# bldc_driver.net
KiCad netlist of a schematic drawn in Altium Designer
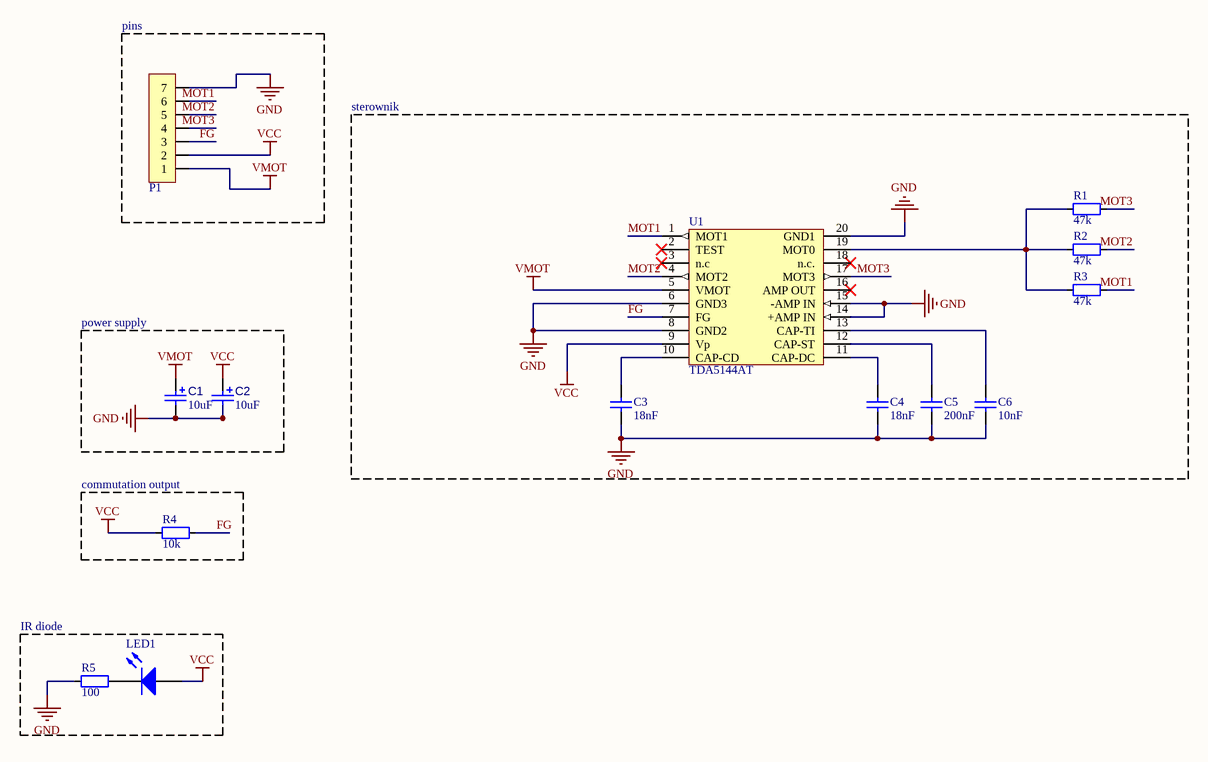
[diagram p0: bldc_driver.SchDoc]

(export (version "E")
  (design (tool "Eeschema 10.0.6"))
  (components
    (comp (ref "C1")
      (value "10uF")
      (footprint "Con_SMD_5x5.5")
      (description "Polar capacitor")
      (libsource (lib "altium_library_onyks") (part "Cap_Pol"))
    )
    (comp (ref "C2")
      (value "10uF")
      (footprint "Con_SMD_5x5.5")
      (description "Polar capacitor")
      (libsource (lib "altium_library_onyks") (part "Cap_Pol"))
    )
    (comp (ref "C3")
      (value "18nF")
      (footprint "0603_CAP")
      (description "Ceramic capacitor")
      (fields (field (name "Comment") "Cap"))
      (libsource (lib "altium_library_onyks") (part "Cap"))
    )
    (comp (ref "C4")
      (value "18nF")
      (footprint "0603_CAP")
      (description "Ceramic capacitor")
      (fields (field (name "Comment") "Cap"))
      (libsource (lib "altium_library_onyks") (part "Cap"))
    )
    (comp (ref "C5")
      (value "200nF")
      (footprint "0603_CAP")
      (description "Ceramic capacitor")
      (fields (field (name "Comment") "Cap"))
      (libsource (lib "altium_library_onyks") (part "Cap"))
    )
    (comp (ref "C6")
      (value "10nF")
      (footprint "0603_CAP")
      (description "Ceramic capacitor")
      (fields (field (name "Comment") "Cap"))
      (libsource (lib "altium_library_onyks") (part "Cap"))
    )
    (comp (ref "LED1")
      (value "RED")
      (footprint "VSMB2020X01")
      (description "Light-emitting diode")
      (libsource (lib "altium_library_onyks") (part "LED"))
    )
    (comp (ref "P1")
      (value "HDR1X7")
      (footprint "HDR1X7")
      (description "Header, 7-Pin")
      (fields (field (name "PUBLISHER") "Altium Limited"))
      (libsource (lib "altium_library_onyks") (part "HDR1X7"))
    )
    (comp (ref "R1")
      (value "47k")
      (footprint "0603_RES")
      (description "Resistior")
      (libsource (lib "altium_library_onyks") (part "RES"))
    )
    (comp (ref "R2")
      (value "47k")
      (footprint "0603_RES")
      (description "Resistior")
      (libsource (lib "altium_library_onyks") (part "RES"))
    )
    (comp (ref "R3")
      (value "47k")
      (footprint "0603_RES")
      (description "Resistior")
      (libsource (lib "altium_library_onyks") (part "RES"))
    )
    (comp (ref "R4")
      (value "10k")
      (footprint "0603_RES")
      (description "Resistior")
      (libsource (lib "altium_library_onyks") (part "RES"))
    )
    (comp (ref "R5")
      (value "100")
      (footprint "0603_RES")
      (description "Resistior")
      (libsource (lib "altium_library_onyks") (part "RES"))
    )
    (comp (ref "U1")
      (value "TDA5144AT")
      (footprint "SO20")
      (description "driver TDA5144AT")
      (libsource (lib "altium_library_onyks") (part "driver_TDA5144AT"))
    )
  )
  (nets
    (net (code "1") (name "/FG") (class "Default")
      (node (ref "P1") (pin "3") (pinfunction "3_3") (pintype "passive"))
      (node (ref "R4") (pin "2") (pinfunction "2_2") (pintype "passive"))
      (node (ref "U1") (pin "7") (pinfunction "FG_7") (pintype "open_collector"))
    )
    (net (code "2") (name "/MOT1") (class "Default")
      (node (ref "P1") (pin "6") (pinfunction "6_6") (pintype "passive"))
      (node (ref "R3") (pin "2") (pinfunction "2_2") (pintype "passive"))
      (node (ref "U1") (pin "1") (pinfunction "MOT1_1") (pintype "output"))
    )
    (net (code "3") (name "/MOT2") (class "Default")
      (node (ref "P1") (pin "5") (pinfunction "5_5") (pintype "passive"))
      (node (ref "R2") (pin "2") (pinfunction "2_2") (pintype "passive"))
      (node (ref "U1") (pin "4") (pinfunction "MOT2_4") (pintype "output"))
    )
    (net (code "4") (name "/MOT3") (class "Default")
      (node (ref "P1") (pin "4") (pinfunction "4_4") (pintype "passive"))
      (node (ref "R1") (pin "2") (pinfunction "2_2") (pintype "passive"))
      (node (ref "U1") (pin "17") (pinfunction "MOT3_17") (pintype "output"))
    )
    (net (code "5") (name "GND") (class "Default")
      (node (ref "C1") (pin "2") (pinfunction "2_2") (pintype "passive"))
      (node (ref "C2") (pin "2") (pinfunction "2_2") (pintype "passive"))
      (node (ref "C3") (pin "1") (pinfunction "1_1") (pintype "passive"))
      (node (ref "C4") (pin "1") (pinfunction "1_1") (pintype "passive"))
      (node (ref "C5") (pin "1") (pinfunction "1_1") (pintype "passive"))
      (node (ref "C6") (pin "1") (pinfunction "1_1") (pintype "passive"))
      (node (ref "P1") (pin "7") (pinfunction "7_7") (pintype "passive"))
      (node (ref "R5") (pin "1") (pinfunction "1_1") (pintype "passive"))
      (node (ref "U1") (pin "14") (pinfunction "+AMP_IN_14") (pintype "input"))
      (node (ref "U1") (pin "15") (pinfunction "-AMP_IN_15") (pintype "input"))
      (node (ref "U1") (pin "20") (pinfunction "GND1_20") (pintype "power_in"))
      (node (ref "U1") (pin "6") (pinfunction "GND3_6") (pintype "power_in"))
      (node (ref "U1") (pin "8") (pinfunction "GND2_8") (pintype "power_in"))
    )
    (net (code "6") (name "Net-(LED1-K)") (class "Default")
      (node (ref "LED1") (pin "2") (pinfunction "K_2") (pintype "passive"))
      (node (ref "R5") (pin "2") (pinfunction "2_2") (pintype "passive"))
    )
    (net (code "7") (name "Net-(U1-CAP-CD)") (class "Default")
      (node (ref "C3") (pin "2") (pinfunction "2_2") (pintype "passive"))
      (node (ref "U1") (pin "10") (pinfunction "CAP-CD_10") (pintype "passive"))
    )
    (net (code "8") (name "Net-(U1-CAP-DC)") (class "Default")
      (node (ref "C4") (pin "2") (pinfunction "2_2") (pintype "passive"))
      (node (ref "U1") (pin "11") (pinfunction "CAP-DC_11") (pintype "passive"))
    )
    (net (code "9") (name "Net-(U1-CAP-ST)") (class "Default")
      (node (ref "C5") (pin "2") (pinfunction "2_2") (pintype "passive"))
      (node (ref "U1") (pin "12") (pinfunction "CAP-ST_12") (pintype "passive"))
    )
    (net (code "10") (name "Net-(U1-CAP-TI)") (class "Default")
      (node (ref "C6") (pin "2") (pinfunction "2_2") (pintype "passive"))
      (node (ref "U1") (pin "13") (pinfunction "CAP-TI_13") (pintype "passive"))
    )
    (net (code "11") (name "Net-(U1-MOT0)") (class "Default")
      (node (ref "R1") (pin "1") (pinfunction "1_1") (pintype "passive"))
      (node (ref "R2") (pin "1") (pinfunction "1_1") (pintype "passive"))
      (node (ref "R3") (pin "1") (pinfunction "1_1") (pintype "passive"))
      (node (ref "U1") (pin "19") (pinfunction "MOT0_19") (pintype "passive"))
    )
    (net (code "12") (name "VCC") (class "Default")
      (node (ref "C2") (pin "1") (pinfunction "1_1") (pintype "passive"))
      (node (ref "LED1") (pin "1") (pinfunction "A_1") (pintype "passive"))
      (node (ref "P1") (pin "2") (pinfunction "2_2") (pintype "passive"))
      (node (ref "R4") (pin "1") (pinfunction "1_1") (pintype "passive"))
      (node (ref "U1") (pin "9") (pinfunction "Vp_9") (pintype "power_in"))
    )
    (net (code "13") (name "VMOT") (class "Default")
      (node (ref "C1") (pin "1") (pinfunction "1_1") (pintype "passive"))
      (node (ref "P1") (pin "1") (pinfunction "1_1") (pintype "passive"))
      (node (ref "U1") (pin "5") (pinfunction "VMOT_5") (pintype "power_in"))
    )
    (net (code "14") (name "unconnected-(U1-AMP_OUT-Pad16)") (class "Default")
      (node (ref "U1") (pin "16") (pinfunction "AMP_OUT_16") (pintype "open_collector+no_connect"))
    )
    (net (code "15") (name "unconnected-(U1-TEST-Pad2)") (class "Default")
      (node (ref "U1") (pin "2") (pinfunction "TEST_2") (pintype "passive+no_connect"))
    )
    (net (code "16") (name "unconnected-(U1-n.c-Pad3)") (class "Default")
      (node (ref "U1") (pin "3") (pinfunction "n.c_3") (pintype "passive+no_connect"))
    )
    (net (code "17") (name "unconnected-(U1-n.c.-Pad18)") (class "Default")
      (node (ref "U1") (pin "18") (pinfunction "n.c._18") (pintype "passive+no_connect"))
    )
  )
)
